# power_switch_led_breakout.net
KiCad netlist of a schematic drawn in EAGLE
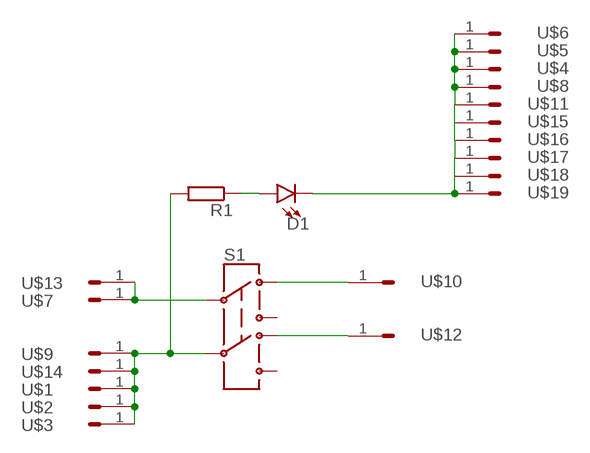
[diagram p0: schematic, sheet 1]

(export (version "E")
  (design (tool "Eeschema 10.0.6"))
  (components
    (comp (ref "D1")
      (value "LED5MM")
      (footprint "eagle-import:LED_5MM")
      (libsource (lib "eagle-import") (part "LED5MM"))
    )
    (comp (ref "R1")
      (value "RESISTORRESISTOR/UPRIGHT/7.5")
      (footprint "eagle-import:RESISTOR_7.5")
      (libsource (lib "eagle-import") (part "RESISTORRESISTOR/UPRIGHT/7.5"))
    )
    (comp (ref "S1")
      (value "SWITCH-DPDTPTH1")
      (footprint "eagle-import:SWITCH-DPDT_SUBMINIATURE")
      (libsource (lib "eagle-import") (part "SWITCH-DPDTPTH1"))
    )
    (comp (ref "U$1")
      (value "HEADER/MALE/01NOBORDER")
      (footprint "eagle-import:HEADER_MALE_01_NOBORDER")
      (libsource (lib "eagle-import") (part "HEADER/MALE/01NOBORDER"))
    )
    (comp (ref "U$2")
      (value "HEADER/MALE/01NOBORDER")
      (footprint "eagle-import:HEADER_MALE_01_NOBORDER")
      (libsource (lib "eagle-import") (part "HEADER/MALE/01NOBORDER"))
    )
    (comp (ref "U$3")
      (value "HEADER/MALE/01NOBORDER")
      (footprint "eagle-import:HEADER_MALE_01_NOBORDER")
      (libsource (lib "eagle-import") (part "HEADER/MALE/01NOBORDER"))
    )
    (comp (ref "U$4")
      (value "HEADER/MALE/01NOBORDER")
      (footprint "eagle-import:HEADER_MALE_01_NOBORDER")
      (libsource (lib "eagle-import") (part "HEADER/MALE/01NOBORDER"))
    )
    (comp (ref "U$5")
      (value "HEADER/MALE/01NOBORDER")
      (footprint "eagle-import:HEADER_MALE_01_NOBORDER")
      (libsource (lib "eagle-import") (part "HEADER/MALE/01NOBORDER"))
    )
    (comp (ref "U$6")
      (value "HEADER/MALE/01NOBORDER")
      (footprint "eagle-import:HEADER_MALE_01_NOBORDER")
      (libsource (lib "eagle-import") (part "HEADER/MALE/01NOBORDER"))
    )
    (comp (ref "U$7")
      (value "HEADER/MALE/01NOBORDER")
      (footprint "eagle-import:HEADER_MALE_01_NOBORDER")
      (libsource (lib "eagle-import") (part "HEADER/MALE/01NOBORDER"))
    )
    (comp (ref "U$8")
      (value "HEADER/MALE/01NOBORDER")
      (footprint "eagle-import:HEADER_MALE_01_NOBORDER")
      (libsource (lib "eagle-import") (part "HEADER/MALE/01NOBORDER"))
    )
    (comp (ref "U$9")
      (value "HEADER/MALE/01NOBORDER")
      (footprint "eagle-import:HEADER_MALE_01_NOBORDER")
      (libsource (lib "eagle-import") (part "HEADER/MALE/01NOBORDER"))
    )
    (comp (ref "U$10")
      (value "HEADER/MALE/01NOBORDER")
      (footprint "eagle-import:HEADER_MALE_01_NOBORDER")
      (libsource (lib "eagle-import") (part "HEADER/MALE/01NOBORDER"))
    )
    (comp (ref "U$11")
      (value "HEADER/MALE/01NOBORDER")
      (footprint "eagle-import:HEADER_MALE_01_NOBORDER")
      (libsource (lib "eagle-import") (part "HEADER/MALE/01NOBORDER"))
    )
    (comp (ref "U$12")
      (value "HEADER/MALE/01NOBORDER")
      (footprint "eagle-import:HEADER_MALE_01_NOBORDER")
      (libsource (lib "eagle-import") (part "HEADER/MALE/01NOBORDER"))
    )
    (comp (ref "U$13")
      (value "HEADER/MALE/01NOBORDER")
      (footprint "eagle-import:HEADER_MALE_01_NOBORDER")
      (libsource (lib "eagle-import") (part "HEADER/MALE/01NOBORDER"))
    )
    (comp (ref "U$14")
      (value "HEADER/MALE/01NOBORDER")
      (footprint "eagle-import:HEADER_MALE_01_NOBORDER")
      (libsource (lib "eagle-import") (part "HEADER/MALE/01NOBORDER"))
    )
    (comp (ref "U$15")
      (value "HEADER/MALE/01NOBORDER")
      (footprint "eagle-import:HEADER_MALE_01_NOBORDER")
      (libsource (lib "eagle-import") (part "HEADER/MALE/01NOBORDER"))
    )
    (comp (ref "U$16")
      (value "HEADER/MALE/01NOBORDER")
      (footprint "eagle-import:HEADER_MALE_01_NOBORDER")
      (libsource (lib "eagle-import") (part "HEADER/MALE/01NOBORDER"))
    )
    (comp (ref "U$17")
      (value "HEADER/MALE/01NOBORDER")
      (footprint "eagle-import:HEADER_MALE_01_NOBORDER")
      (libsource (lib "eagle-import") (part "HEADER/MALE/01NOBORDER"))
    )
    (comp (ref "U$18")
      (value "HEADER/MALE/01NOBORDER")
      (footprint "eagle-import:HEADER_MALE_01_NOBORDER")
      (libsource (lib "eagle-import") (part "HEADER/MALE/01NOBORDER"))
    )
    (comp (ref "U$19")
      (value "HEADER/MALE/01NOBORDER")
      (footprint "eagle-import:HEADER_MALE_01_NOBORDER")
      (libsource (lib "eagle-import") (part "HEADER/MALE/01NOBORDER"))
    )
  )
  (nets
    (net (code "1") (name "Net-(D1-C)") (class "Default")
      (node (ref "D1") (pin "K") (pinfunction "C_K") (pintype "passive"))
      (node (ref "U$11") (pin "1") (pinfunction "3_1") (pintype "passive"))
      (node (ref "U$15") (pin "1") (pinfunction "3_1") (pintype "passive"))
      (node (ref "U$16") (pin "1") (pinfunction "3_1") (pintype "passive"))
      (node (ref "U$17") (pin "1") (pinfunction "3_1") (pintype "passive"))
      (node (ref "U$18") (pin "1") (pinfunction "3_1") (pintype "passive"))
      (node (ref "U$19") (pin "1") (pinfunction "3_1") (pintype "passive"))
      (node (ref "U$4") (pin "1") (pinfunction "3_1") (pintype "passive"))
      (node (ref "U$5") (pin "1") (pinfunction "3_1") (pintype "passive"))
      (node (ref "U$6") (pin "1") (pinfunction "3_1") (pintype "passive"))
      (node (ref "U$8") (pin "1") (pinfunction "3_1") (pintype "passive"))
    )
    (net (code "2") (name "Net-(D1-PadA)") (class "Default")
      (node (ref "D1") (pin "A") (pinfunction "A_A") (pintype "passive"))
      (node (ref "R1") (pin "1") (pinfunction "1_1") (pintype "passive"))
    )
    (net (code "3") (name "Net-(U$1-3)") (class "Default")
      (node (ref "R1") (pin "2") (pinfunction "2_2") (pintype "passive"))
      (node (ref "S1") (pin "5") (pinfunction "5_5") (pintype "bidirectional"))
      (node (ref "U$1") (pin "1") (pinfunction "3_1") (pintype "passive"))
      (node (ref "U$14") (pin "1") (pinfunction "3_1") (pintype "passive"))
      (node (ref "U$2") (pin "1") (pinfunction "3_1") (pintype "passive"))
      (node (ref "U$3") (pin "1") (pinfunction "3_1") (pintype "passive"))
      (node (ref "U$9") (pin "1") (pinfunction "3_1") (pintype "passive"))
    )
    (net (code "4") (name "Net-(U$10-3)") (class "Default")
      (node (ref "S1") (pin "1") (pinfunction "1_1") (pintype "bidirectional"))
      (node (ref "U$10") (pin "1") (pinfunction "3_1") (pintype "passive"))
    )
    (net (code "5") (name "Net-(U$12-3)") (class "Default")
      (node (ref "S1") (pin "4") (pinfunction "4_4") (pintype "bidirectional"))
      (node (ref "U$12") (pin "1") (pinfunction "3_1") (pintype "passive"))
    )
    (net (code "6") (name "Net-(U$13-3)") (class "Default")
      (node (ref "S1") (pin "2") (pinfunction "2_2") (pintype "bidirectional"))
      (node (ref "U$13") (pin "1") (pinfunction "3_1") (pintype "passive"))
      (node (ref "U$7") (pin "1") (pinfunction "3_1") (pintype "passive"))
    )
    (net (code "7") (name "unconnected-(S1-Pad3)") (class "Default")
      (node (ref "S1") (pin "3") (pinfunction "3_3") (pintype "bidirectional"))
    )
    (net (code "8") (name "unconnected-(S1-Pad6)") (class "Default")
      (node (ref "S1") (pin "6") (pinfunction "6_6") (pintype "bidirectional"))
    )
  )
)
